# OMC_Unit_200316.net
KiCad netlist of a schematic drawn in Altium Designer
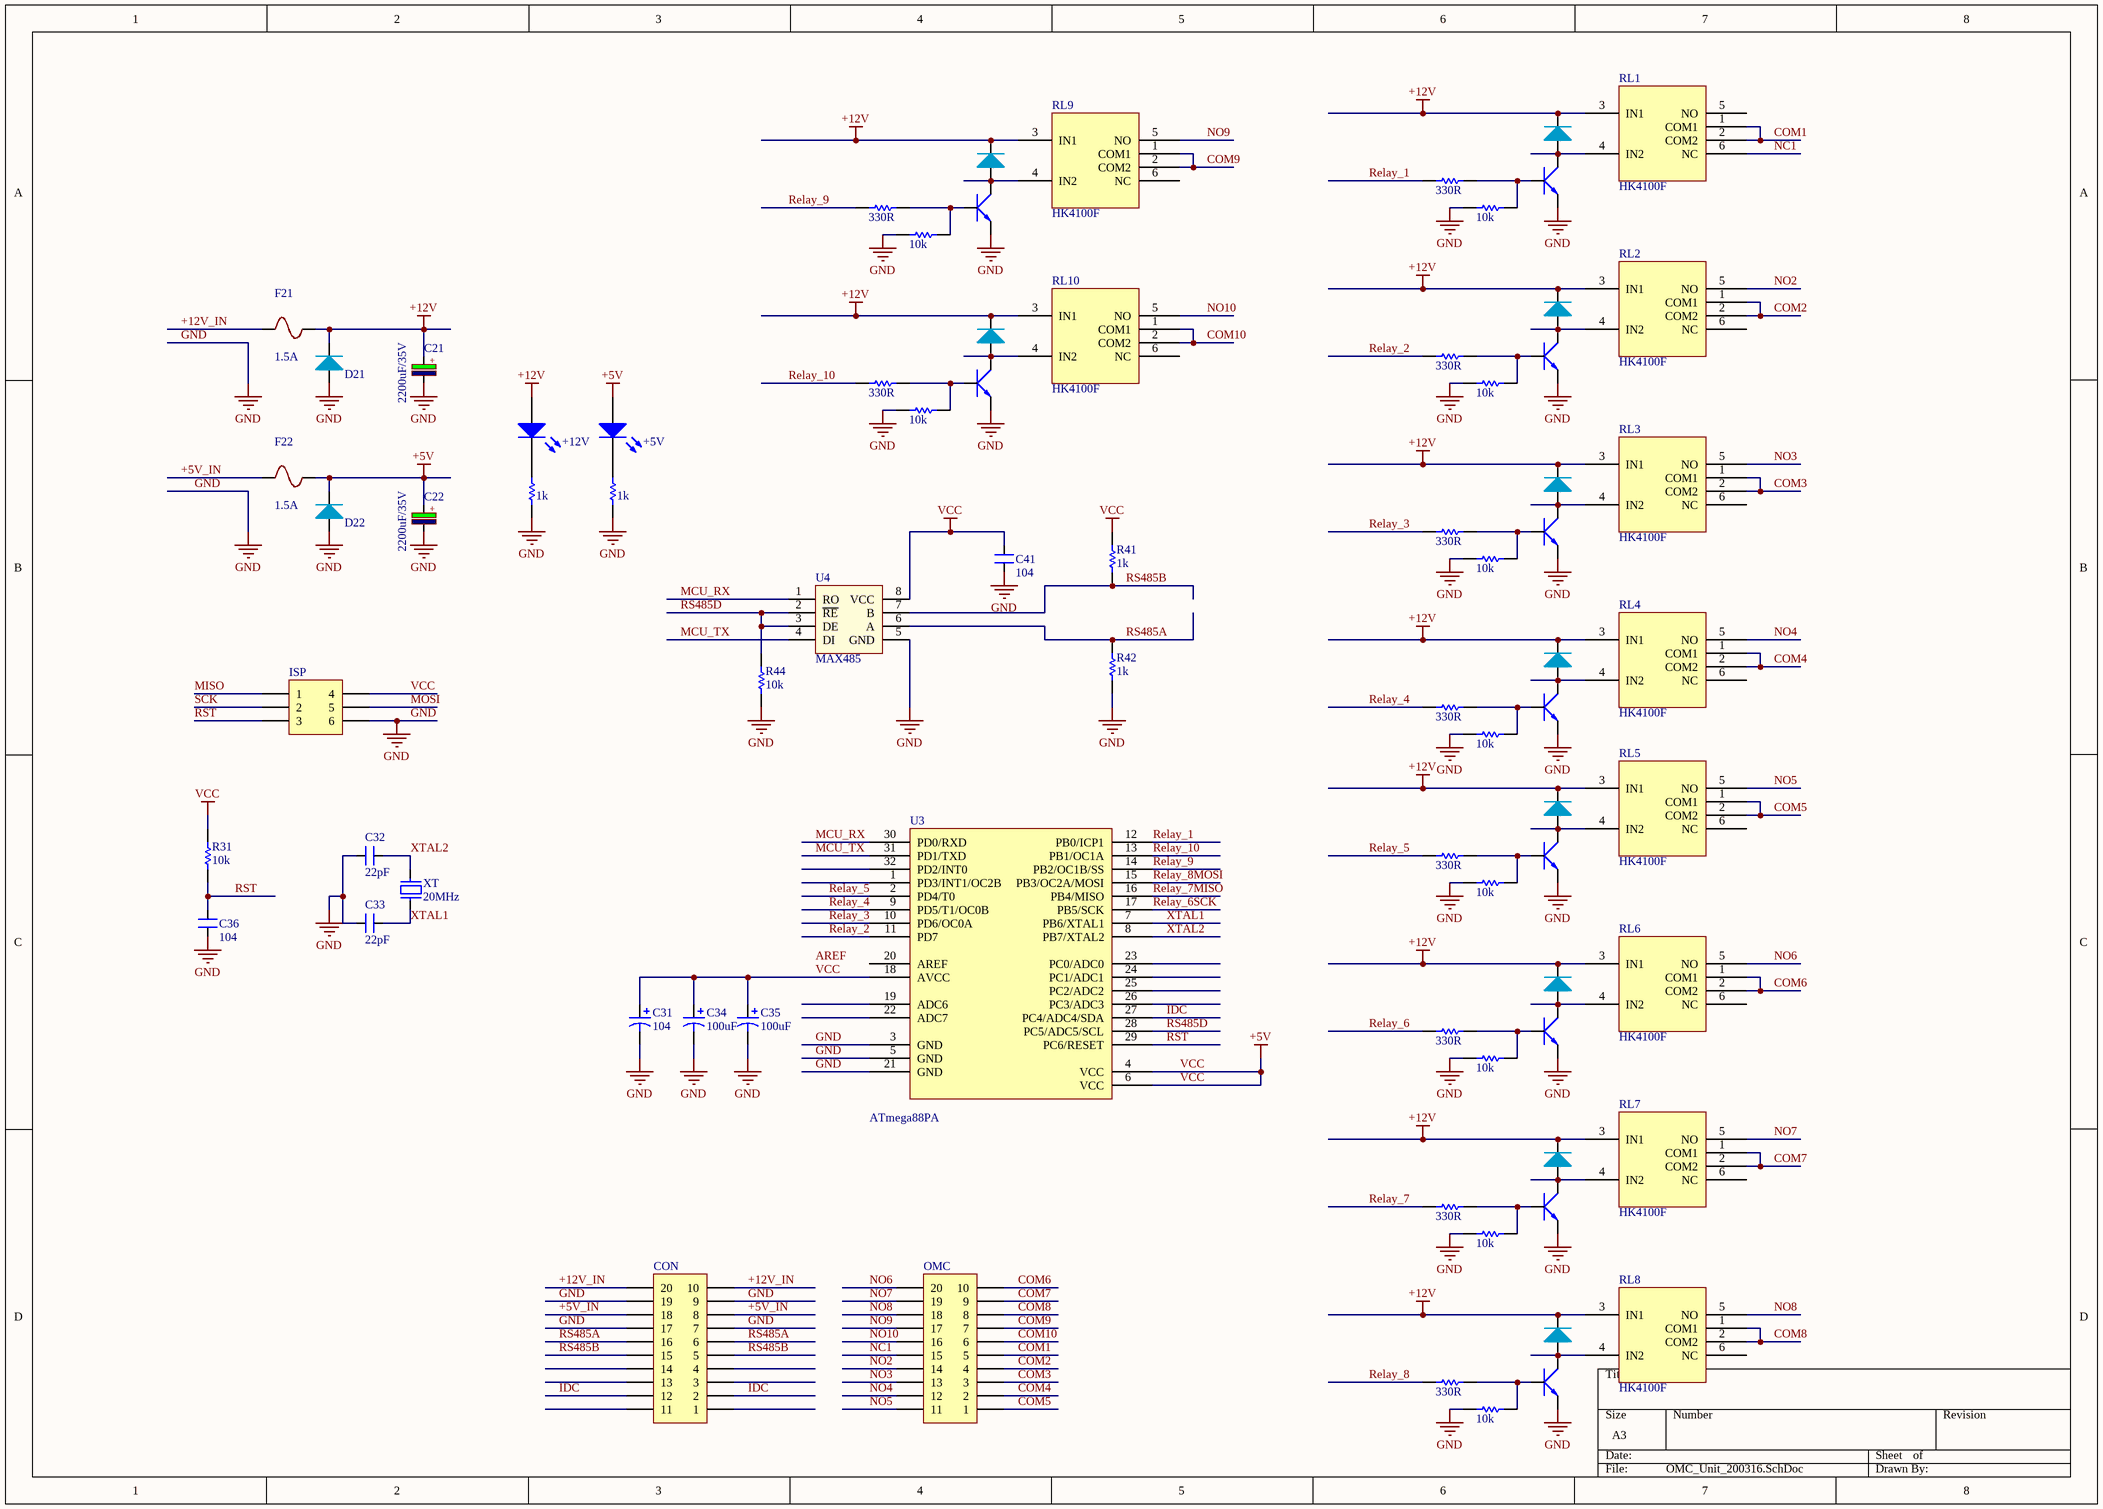
[diagram p0: OMC_Unit_200316.SchDoc]

(export (version "E")
  (design (tool "Eeschema 10.0.6"))
  (components
    (comp (ref "+5V") (value "Led") (footprint "LED 5mm RED") (libsource (lib "Tuan") (part "Led")))
    (comp (ref "+12V") (value "Led") (footprint "LED 5mm RED") (libsource (lib "Tuan") (part "Led")))
    (comp (ref "C21")
      (value "2200uF/35V")
      (footprint "PBL - SMD Packages:CAP_ELEC_SIZE_G")
      (description "Cap 1000uF/16V - 220uF/50V")
      (libsource (lib "heromap") (part "CP4"))
    )
    (comp (ref "C22")
      (value "2200uF/35V")
      (footprint "PBL - SMD Packages:CAP_ELEC_SIZE_G")
      (description "Cap 1000uF/16V - 220uF/50V")
      (libsource (lib "heromap") (part "CP4"))
    )
    (comp (ref "C31")
      (value "104")
      (footprint "CAPC2012N_F")
      (fields (field (name "Comment") "Cap"))
      (libsource (lib "Tuan") (part "Cap"))
    )
    (comp (ref "C32")
      (value "22pF")
      (footprint "CAPC1608N")
      (fields (field (name "Comment") "CAP NP"))
      (libsource (lib "Tuan") (part "CAP NP"))
    )
    (comp (ref "C33")
      (value "22pF")
      (footprint "CAPC1608N")
      (fields (field (name "Comment") "CAP NP"))
      (libsource (lib "Tuan") (part "CAP NP"))
    )
    (comp (ref "C34")
      (value "100uF")
      (footprint "CAPC2012N_F")
      (fields (field (name "Comment") "Cap"))
      (libsource (lib "Tuan") (part "Cap"))
    )
    (comp (ref "C35")
      (value "100uF")
      (footprint "CAPC2012N_F")
      (fields (field (name "Comment") "Cap"))
      (libsource (lib "Tuan") (part "Cap"))
    )
    (comp (ref "C36")
      (value "104")
      (footprint "CAPC1608N")
      (fields (field (name "Comment") "CAP NP"))
      (libsource (lib "Tuan") (part "CAP NP"))
    )
    (comp (ref "C41")
      (value "104")
      (footprint "CAPC2012N_F")
      (fields (field (name "Comment") "100nF/104"))
      (libsource (lib "Tuan") (part "CAP NP"))
    )
    (comp (ref "CON")
      (value "Header 10X2A")
      (footprint "OMC10")
      (description "Header, 10-Pin, Dual row")
      (fields (field (name "PUBLISHER") "Altium Limited"))
      (libsource (lib "Miscellaneous Connectors") (part "Header 10X2A"))
    )
    (comp (ref "D21") (value "Diode") (footprint "DO-214AC") (libsource (lib "Tuan") (part "Diode")))
    (comp (ref "D22") (value "Diode") (footprint "DO-214AC") (libsource (lib "Tuan") (part "Diode")))
    (comp (ref "Do1") (value "M7") (footprint "DO-214AC") (libsource (lib "Tuan") (part "Diode")))
    (comp (ref "Do2") (value "M7") (footprint "DO-214AC") (libsource (lib "Tuan") (part "Diode")))
    (comp (ref "Do3") (value "M7") (footprint "DO-214AC") (libsource (lib "Tuan") (part "Diode")))
    (comp (ref "Do4") (value "M7") (footprint "DO-214AC") (libsource (lib "Tuan") (part "Diode")))
    (comp (ref "Do5") (value "M7") (footprint "DO-214AC") (libsource (lib "Tuan") (part "Diode")))
    (comp (ref "Do6") (value "M7") (footprint "DO-214AC") (libsource (lib "Tuan") (part "Diode")))
    (comp (ref "Do7") (value "M7") (footprint "DO-214AC") (libsource (lib "Tuan") (part "Diode")))
    (comp (ref "Do8") (value "M7") (footprint "DO-214AC") (libsource (lib "Tuan") (part "Diode")))
    (comp (ref "Do9") (value "M7") (footprint "DO-214AC") (libsource (lib "Tuan") (part "Diode")))
    (comp (ref "Do10") (value "M7") (footprint "DO-214AC") (libsource (lib "Tuan") (part "Diode")))
    (comp (ref "F21") (value "1.5A") (footprint "FUSE_SR-5-BK") (libsource (lib "Tuan") (part "Fuse")))
    (comp (ref "F22") (value "1.5A") (footprint "FUSE_SR-5-BK") (libsource (lib "Tuan") (part "Fuse")))
    (comp (ref "ISP")
      (value "Header 3X2A")
      (footprint "HDR2X3_CEN")
      (description "Header, 3-Pin, Dual row")
      (fields (field (name "PUBLISHER") "Altium Limited"))
      (libsource (lib "Miscellaneous Connectors") (part "Header 3X2A"))
    )
    (comp (ref "OMC")
      (value "Header 10X2A")
      (footprint "OMC10")
      (description "Header, 10-Pin, Dual row")
      (fields (field (name "PUBLISHER") "Altium Limited"))
      (libsource (lib "Miscellaneous Connectors") (part "Header 10X2A"))
    )
    (comp (ref "Qo1")
      (value "C828")
      (footprint "SOT23 TOP")
      (description "Transistor C828 C1815....")
      (libsource (lib "Tuan") (part "NPN"))
    )
    (comp (ref "Qo2")
      (value "C828")
      (footprint "SOT23 TOP")
      (description "Transistor C828 C1815....")
      (libsource (lib "Tuan") (part "NPN"))
    )
    (comp (ref "Qo3")
      (value "C828")
      (footprint "SOT23 TOP")
      (description "Transistor C828 C1815....")
      (libsource (lib "Tuan") (part "NPN"))
    )
    (comp (ref "Qo4")
      (value "C828")
      (footprint "SOT23 TOP")
      (description "Transistor C828 C1815....")
      (libsource (lib "Tuan") (part "NPN"))
    )
    (comp (ref "Qo5")
      (value "C828")
      (footprint "SOT23 TOP")
      (description "Transistor C828 C1815....")
      (libsource (lib "Tuan") (part "NPN"))
    )
    (comp (ref "Qo6")
      (value "C828")
      (footprint "SOT23 TOP")
      (description "Transistor C828 C1815....")
      (libsource (lib "Tuan") (part "NPN"))
    )
    (comp (ref "Qo7")
      (value "C828")
      (footprint "SOT23 TOP")
      (description "Transistor C828 C1815....")
      (libsource (lib "Tuan") (part "NPN"))
    )
    (comp (ref "Qo8")
      (value "C828")
      (footprint "SOT23 TOP")
      (description "Transistor C828 C1815....")
      (libsource (lib "Tuan") (part "NPN"))
    )
    (comp (ref "Qo9")
      (value "C828")
      (footprint "SOT23 TOP")
      (description "Transistor C828 C1815....")
      (libsource (lib "Tuan") (part "NPN"))
    )
    (comp (ref "Qo10")
      (value "C828")
      (footprint "SOT23 TOP")
      (description "Transistor C828 C1815....")
      (libsource (lib "Tuan") (part "NPN"))
    )
    (comp (ref "R21")
      (value "1k")
      (footprint "RESC2012N_F")
      (fields (field (name "Comment") "Res_0805_1k"))
      (libsource (lib "Tuan") (part "Res"))
    )
    (comp (ref "R22")
      (value "1k")
      (footprint "RESC2012N_F")
      (fields (field (name "Comment") "Res_0805_1k"))
      (libsource (lib "Tuan") (part "Res"))
    )
    (comp (ref "R31")
      (value "10k")
      (footprint "RESC1608N_ZERO")
      (fields (field (name "Comment") "Res"))
      (libsource (lib "Tuan") (part "Res"))
    )
    (comp (ref "R41")
      (value "1k")
      (footprint "RESC1608N_ZERO")
      (description "Tro dan")
      (libsource (lib "GPS_Clock_v12") (part "Res"))
    )
    (comp (ref "R42")
      (value "1k")
      (footprint "RESC1608N_ZERO")
      (description "Tro dan")
      (libsource (lib "GPS_Clock_v12") (part "Res"))
    )
    (comp (ref "R44")
      (value "10k")
      (footprint "RESC1608N_ZERO")
      (description "Tro dan")
      (fields (field (name "Comment") "330R"))
      (libsource (lib "GPS_Clock_v12") (part "Res"))
    )
    (comp (ref "RL1") (value "HK4100F") (footprint "HK4100F") (libsource (lib "Tuan") (part "HK4100F")))
    (comp (ref "RL2") (value "HK4100F") (footprint "HK4100F") (libsource (lib "Tuan") (part "HK4100F")))
    (comp (ref "RL3") (value "HK4100F") (footprint "HK4100F") (libsource (lib "Tuan") (part "HK4100F")))
    (comp (ref "RL4") (value "HK4100F") (footprint "HK4100F") (libsource (lib "Tuan") (part "HK4100F")))
    (comp (ref "RL5") (value "HK4100F") (footprint "HK4100F") (libsource (lib "Tuan") (part "HK4100F")))
    (comp (ref "RL6") (value "HK4100F") (footprint "HK4100F") (libsource (lib "Tuan") (part "HK4100F")))
    (comp (ref "RL7") (value "HK4100F") (footprint "HK4100F") (libsource (lib "Tuan") (part "HK4100F")))
    (comp (ref "RL8") (value "HK4100F") (footprint "HK4100F") (libsource (lib "Tuan") (part "HK4100F")))
    (comp (ref "RL9") (value "HK4100F") (footprint "HK4100F") (libsource (lib "Tuan") (part "HK4100F")))
    (comp (ref "RL10") (value "HK4100F") (footprint "HK4100F") (libsource (lib "Tuan") (part "HK4100F")))
    (comp (ref "Rp1")
      (value "10k")
      (footprint "RESC1608N_ZERO")
      (fields (field (name "Comment") "Res"))
      (libsource (lib "Tuan") (part "Res"))
    )
    (comp (ref "Rp2")
      (value "10k")
      (footprint "RESC1608N_ZERO")
      (fields (field (name "Comment") "Res"))
      (libsource (lib "Tuan") (part "Res"))
    )
    (comp (ref "Rp3")
      (value "10k")
      (footprint "RESC1608N_ZERO")
      (fields (field (name "Comment") "Res"))
      (libsource (lib "Tuan") (part "Res"))
    )
    (comp (ref "Rp4")
      (value "10k")
      (footprint "RESC1608N_ZERO")
      (fields (field (name "Comment") "Res"))
      (libsource (lib "Tuan") (part "Res"))
    )
    (comp (ref "Rp5")
      (value "10k")
      (footprint "RESC1608N_ZERO")
      (fields (field (name "Comment") "Res"))
      (libsource (lib "Tuan") (part "Res"))
    )
    (comp (ref "Rp6")
      (value "10k")
      (footprint "RESC1608N_ZERO")
      (fields (field (name "Comment") "Res"))
      (libsource (lib "Tuan") (part "Res"))
    )
    (comp (ref "Rp7")
      (value "10k")
      (footprint "RESC1608N_ZERO")
      (fields (field (name "Comment") "Res"))
      (libsource (lib "Tuan") (part "Res"))
    )
    (comp (ref "Rp8")
      (value "10k")
      (footprint "RESC1608N_ZERO")
      (fields (field (name "Comment") "Res"))
      (libsource (lib "Tuan") (part "Res"))
    )
    (comp (ref "Rp9")
      (value "10k")
      (footprint "RESC1608N_ZERO")
      (fields (field (name "Comment") "Res"))
      (libsource (lib "Tuan") (part "Res"))
    )
    (comp (ref "Rp10")
      (value "10k")
      (footprint "RESC1608N_ZERO")
      (fields (field (name "Comment") "Res"))
      (libsource (lib "Tuan") (part "Res"))
    )
    (comp (ref "Rr1")
      (value "330R")
      (footprint "RESC1608N_ZERO")
      (fields (field (name "Comment") "Res"))
      (libsource (lib "Tuan") (part "Res"))
    )
    (comp (ref "Rr2")
      (value "330R")
      (footprint "RESC1608N_ZERO")
      (fields (field (name "Comment") "Res"))
      (libsource (lib "Tuan") (part "Res"))
    )
    (comp (ref "Rr3")
      (value "330R")
      (footprint "RESC1608N_ZERO")
      (fields (field (name "Comment") "Res"))
      (libsource (lib "Tuan") (part "Res"))
    )
    (comp (ref "Rr4")
      (value "330R")
      (footprint "RESC1608N_ZERO")
      (fields (field (name "Comment") "Res"))
      (libsource (lib "Tuan") (part "Res"))
    )
    (comp (ref "Rr5")
      (value "330R")
      (footprint "RESC1608N_ZERO")
      (fields (field (name "Comment") "Res"))
      (libsource (lib "Tuan") (part "Res"))
    )
    (comp (ref "Rr6")
      (value "330R")
      (footprint "RESC1608N_ZERO")
      (fields (field (name "Comment") "Res"))
      (libsource (lib "Tuan") (part "Res"))
    )
    (comp (ref "Rr7")
      (value "330R")
      (footprint "RESC1608N_ZERO")
      (fields (field (name "Comment") "Res"))
      (libsource (lib "Tuan") (part "Res"))
    )
    (comp (ref "Rr8")
      (value "330R")
      (footprint "RESC1608N_ZERO")
      (fields (field (name "Comment") "Res"))
      (libsource (lib "Tuan") (part "Res"))
    )
    (comp (ref "Rr9")
      (value "330R")
      (footprint "RESC1608N_ZERO")
      (fields (field (name "Comment") "Res"))
      (libsource (lib "Tuan") (part "Res"))
    )
    (comp (ref "Rr10")
      (value "330R")
      (footprint "RESC1608N_ZERO")
      (fields (field (name "Comment") "Res"))
      (libsource (lib "Tuan") (part "Res"))
    )
    (comp (ref "U3")
      (value "ATmega88PA")
      (footprint "32PIN")
      (description "ATmega48/168/328")
      (libsource (lib "Tuan") (part "ATmega48/168/328"))
    )
    (comp (ref "U4")
      (value "MAX485")
      (footprint "SO-8")
      (description "RS232 - RS485 (Same sn75176)")
      (libsource (lib "heromap") (part "MAX485"))
    )
    (comp (ref "XT") (value "20MHz") (footprint "XT2") (libsource (lib "Tuan") (part "Crystal")))
  )
  (nets
    (net (code "1") (name "+5V") (class "Default")
      (node (ref "+5V") (pin "1") (pinfunction "A_1") (pintype "passive"))
      (node (ref "C22") (pin "1") (pinfunction "1_1") (pintype "passive"))
      (node (ref "C31") (pin "1") (pinfunction "1_1") (pintype "passive"))
      (node (ref "C34") (pin "1") (pinfunction "1_1") (pintype "passive"))
      (node (ref "C35") (pin "1") (pinfunction "1_1") (pintype "passive"))
      (node (ref "C41") (pin "2") (pinfunction "2_2") (pintype "passive"))
      (node (ref "D22") (pin "2") (pinfunction "K_2") (pintype "passive"))
      (node (ref "F22") (pin "2") (pinfunction "2_2") (pintype "passive"))
      (node (ref "ISP") (pin "4") (pinfunction "4_4") (pintype "passive"))
      (node (ref "R31") (pin "2") (pinfunction "2_2") (pintype "passive"))
      (node (ref "R41") (pin "2") (pinfunction "2_2") (pintype "passive"))
      (node (ref "U3") (pin "18") (pinfunction "AVCC_18") (pintype "passive"))
      (node (ref "U3") (pin "4") (pinfunction "VCC_4") (pintype "passive"))
      (node (ref "U3") (pin "6") (pinfunction "VCC_6") (pintype "passive"))
      (node (ref "U4") (pin "8") (pinfunction "VCC_8") (pintype "passive"))
    )
    (net (code "2") (name "+12V") (class "Default")
      (node (ref "+12V") (pin "1") (pinfunction "A_1") (pintype "passive"))
      (node (ref "C21") (pin "1") (pinfunction "1_1") (pintype "passive"))
      (node (ref "D21") (pin "2") (pinfunction "K_2") (pintype "passive"))
      (node (ref "Do1") (pin "2") (pinfunction "K_2") (pintype "passive"))
      (node (ref "Do10") (pin "2") (pinfunction "K_2") (pintype "passive"))
      (node (ref "Do2") (pin "2") (pinfunction "K_2") (pintype "passive"))
      (node (ref "Do3") (pin "2") (pinfunction "K_2") (pintype "passive"))
      (node (ref "Do4") (pin "2") (pinfunction "K_2") (pintype "passive"))
      (node (ref "Do5") (pin "2") (pinfunction "K_2") (pintype "passive"))
      (node (ref "Do6") (pin "2") (pinfunction "K_2") (pintype "passive"))
      (node (ref "Do7") (pin "2") (pinfunction "K_2") (pintype "passive"))
      (node (ref "Do8") (pin "2") (pinfunction "K_2") (pintype "passive"))
      (node (ref "Do9") (pin "2") (pinfunction "K_2") (pintype "passive"))
      (node (ref "F21") (pin "2") (pinfunction "2_2") (pintype "passive"))
      (node (ref "RL1") (pin "3") (pinfunction "IN1_3") (pintype "passive"))
      (node (ref "RL10") (pin "3") (pinfunction "IN1_3") (pintype "passive"))
      (node (ref "RL2") (pin "3") (pinfunction "IN1_3") (pintype "passive"))
      (node (ref "RL3") (pin "3") (pinfunction "IN1_3") (pintype "passive"))
      (node (ref "RL4") (pin "3") (pinfunction "IN1_3") (pintype "passive"))
      (node (ref "RL5") (pin "3") (pinfunction "IN1_3") (pintype "passive"))
      (node (ref "RL6") (pin "3") (pinfunction "IN1_3") (pintype "passive"))
      (node (ref "RL7") (pin "3") (pinfunction "IN1_3") (pintype "passive"))
      (node (ref "RL8") (pin "3") (pinfunction "IN1_3") (pintype "passive"))
      (node (ref "RL9") (pin "3") (pinfunction "IN1_3") (pintype "passive"))
    )
    (net (code "3") (name "/+5V_IN") (class "Default")
      (node (ref "CON") (pin "18") (pinfunction "18_18") (pintype "passive"))
      (node (ref "CON") (pin "8") (pinfunction "8_8") (pintype "passive"))
      (node (ref "F22") (pin "1") (pinfunction "1_1") (pintype "passive"))
    )
    (net (code "4") (name "/+12V_IN") (class "Default")
      (node (ref "CON") (pin "10") (pinfunction "10_10") (pintype "passive"))
      (node (ref "CON") (pin "20") (pinfunction "20_20") (pintype "passive"))
      (node (ref "F21") (pin "1") (pinfunction "1_1") (pintype "passive"))
    )
    (net (code "6") (name "/COM1") (class "Default")
      (node (ref "OMC") (pin "5") (pinfunction "5_5") (pintype "passive"))
      (node (ref "RL1") (pin "1") (pinfunction "COM1_1") (pintype "passive"))
      (node (ref "RL1") (pin "2") (pinfunction "COM2_2") (pintype "passive"))
    )
    (net (code "7") (name "/COM2") (class "Default")
      (node (ref "OMC") (pin "4") (pinfunction "4_4") (pintype "passive"))
      (node (ref "RL2") (pin "1") (pinfunction "COM1_1") (pintype "passive"))
      (node (ref "RL2") (pin "2") (pinfunction "COM2_2") (pintype "passive"))
    )
    (net (code "8") (name "/COM3") (class "Default")
      (node (ref "OMC") (pin "3") (pinfunction "3_3") (pintype "passive"))
      (node (ref "RL3") (pin "1") (pinfunction "COM1_1") (pintype "passive"))
      (node (ref "RL3") (pin "2") (pinfunction "COM2_2") (pintype "passive"))
    )
    (net (code "9") (name "/COM4") (class "Default")
      (node (ref "OMC") (pin "2") (pinfunction "2_2") (pintype "passive"))
      (node (ref "RL4") (pin "1") (pinfunction "COM1_1") (pintype "passive"))
      (node (ref "RL4") (pin "2") (pinfunction "COM2_2") (pintype "passive"))
    )
    (net (code "10") (name "/COM5") (class "Default")
      (node (ref "OMC") (pin "1") (pinfunction "1_1") (pintype "passive"))
      (node (ref "RL5") (pin "1") (pinfunction "COM1_1") (pintype "passive"))
      (node (ref "RL5") (pin "2") (pinfunction "COM2_2") (pintype "passive"))
    )
    (net (code "11") (name "/COM6") (class "Default")
      (node (ref "OMC") (pin "10") (pinfunction "10_10") (pintype "passive"))
      (node (ref "RL6") (pin "1") (pinfunction "COM1_1") (pintype "passive"))
      (node (ref "RL6") (pin "2") (pinfunction "COM2_2") (pintype "passive"))
    )
    (net (code "12") (name "/COM7") (class "Default")
      (node (ref "OMC") (pin "9") (pinfunction "9_9") (pintype "passive"))
      (node (ref "RL7") (pin "1") (pinfunction "COM1_1") (pintype "passive"))
      (node (ref "RL7") (pin "2") (pinfunction "COM2_2") (pintype "passive"))
    )
    (net (code "13") (name "/COM8") (class "Default")
      (node (ref "OMC") (pin "8") (pinfunction "8_8") (pintype "passive"))
      (node (ref "RL8") (pin "1") (pinfunction "COM1_1") (pintype "passive"))
      (node (ref "RL8") (pin "2") (pinfunction "COM2_2") (pintype "passive"))
    )
    (net (code "14") (name "/COM9") (class "Default")
      (node (ref "OMC") (pin "7") (pinfunction "7_7") (pintype "passive"))
      (node (ref "RL9") (pin "1") (pinfunction "COM1_1") (pintype "passive"))
      (node (ref "RL9") (pin "2") (pinfunction "COM2_2") (pintype "passive"))
    )
    (net (code "15") (name "/COM10") (class "Default")
      (node (ref "OMC") (pin "6") (pinfunction "6_6") (pintype "passive"))
      (node (ref "RL10") (pin "1") (pinfunction "COM1_1") (pintype "passive"))
      (node (ref "RL10") (pin "2") (pinfunction "COM2_2") (pintype "passive"))
    )
    (net (code "16") (name "/IDC") (class "Default")
      (node (ref "CON") (pin "12") (pinfunction "12_12") (pintype "passive"))
      (node (ref "CON") (pin "2") (pinfunction "2_2") (pintype "passive"))
      (node (ref "U3") (pin "27") (pinfunction "PC4/ADC4/SDA_27") (pintype "passive"))
    )
    (net (code "17") (name "/MCU_RX") (class "Default")
      (node (ref "U3") (pin "30") (pinfunction "PD0/RXD_30") (pintype "passive"))
      (node (ref "U4") (pin "1") (pinfunction "RO_1") (pintype "passive"))
    )
    (net (code "18") (name "/MCU_TX") (class "Default")
      (node (ref "U3") (pin "31") (pinfunction "PD1/TXD_31") (pintype "passive"))
      (node (ref "U4") (pin "4") (pinfunction "DI_4") (pintype "passive"))
    )
    (net (code "19") (name "/MISO") (class "Default")
      (node (ref "ISP") (pin "1") (pinfunction "1_1") (pintype "passive"))
      (node (ref "Rr7") (pin "1") (pinfunction "1_1") (pintype "passive"))
      (node (ref "U3") (pin "16") (pinfunction "PB4/MISO_16") (pintype "passive"))
    )
    (net (code "20") (name "/MOSI") (class "Default")
      (node (ref "ISP") (pin "5") (pinfunction "5_5") (pintype "passive"))
      (node (ref "Rr8") (pin "1") (pinfunction "1_1") (pintype "passive"))
      (node (ref "U3") (pin "15") (pinfunction "PB3/OC2A/MOSI_15") (pintype "passive"))
    )
    (net (code "21") (name "/NC1") (class "Default")
      (node (ref "OMC") (pin "15") (pinfunction "15_15") (pintype "passive"))
      (node (ref "RL1") (pin "6") (pinfunction "NC_6") (pintype "passive"))
    )
    (net (code "22") (name "/NO2") (class "Default")
      (node (ref "OMC") (pin "14") (pinfunction "14_14") (pintype "passive"))
      (node (ref "RL2") (pin "5") (pinfunction "NO_5") (pintype "passive"))
    )
    (net (code "23") (name "/NO3") (class "Default")
      (node (ref "OMC") (pin "13") (pinfunction "13_13") (pintype "passive"))
      (node (ref "RL3") (pin "5") (pinfunction "NO_5") (pintype "passive"))
    )
    (net (code "24") (name "/NO4") (class "Default")
      (node (ref "OMC") (pin "12") (pinfunction "12_12") (pintype "passive"))
      (node (ref "RL4") (pin "5") (pinfunction "NO_5") (pintype "passive"))
    )
    (net (code "25") (name "/NO5") (class "Default")
      (node (ref "OMC") (pin "11") (pinfunction "11_11") (pintype "passive"))
      (node (ref "RL5") (pin "5") (pinfunction "NO_5") (pintype "passive"))
    )
    (net (code "26") (name "/NO6") (class "Default")
      (node (ref "OMC") (pin "20") (pinfunction "20_20") (pintype "passive"))
      (node (ref "RL6") (pin "5") (pinfunction "NO_5") (pintype "passive"))
    )
    (net (code "27") (name "/NO7") (class "Default")
      (node (ref "OMC") (pin "19") (pinfunction "19_19") (pintype "passive"))
      (node (ref "RL7") (pin "5") (pinfunction "NO_5") (pintype "passive"))
    )
    (net (code "28") (name "/NO8") (class "Default")
      (node (ref "OMC") (pin "18") (pinfunction "18_18") (pintype "passive"))
      (node (ref "RL8") (pin "5") (pinfunction "NO_5") (pintype "passive"))
    )
    (net (code "29") (name "/NO9") (class "Default")
      (node (ref "OMC") (pin "17") (pinfunction "17_17") (pintype "passive"))
      (node (ref "RL9") (pin "5") (pinfunction "NO_5") (pintype "passive"))
    )
    (net (code "30") (name "/NO10") (class "Default")
      (node (ref "OMC") (pin "16") (pinfunction "16_16") (pintype "passive"))
      (node (ref "RL10") (pin "5") (pinfunction "NO_5") (pintype "passive"))
    )
    (net (code "31") (name "/RS485A") (class "Default")
      (node (ref "CON") (pin "16") (pinfunction "16_16") (pintype "passive"))
      (node (ref "CON") (pin "6") (pinfunction "6_6") (pintype "passive"))
      (node (ref "R42") (pin "2") (pinfunction "2_2") (pintype "passive"))
      (node (ref "U4") (pin "6") (pinfunction "A_6") (pintype "passive"))
    )
    (net (code "32") (name "/RS485B") (class "Default")
      (node (ref "CON") (pin "15") (pinfunction "15_15") (pintype "passive"))
      (node (ref "CON") (pin "5") (pinfunction "5_5") (pintype "passive"))
      (node (ref "R41") (pin "1") (pinfunction "1_1") (pintype "passive"))
      (node (ref "U4") (pin "7") (pinfunction "B_7") (pintype "passive"))
    )
    (net (code "33") (name "/RS485D") (class "Default")
      (node (ref "R44") (pin "2") (pinfunction "2_2") (pintype "passive"))
      (node (ref "U3") (pin "28") (pinfunction "PC5/ADC5/SCL_28") (pintype "passive"))
      (node (ref "U4") (pin "2") (pinfunction "~{RE}_2") (pintype "passive"))
      (node (ref "U4") (pin "3") (pinfunction "DE_3") (pintype "passive"))
    )
    (net (code "34") (name "/RST") (class "Default")
      (node (ref "C36") (pin "2") (pinfunction "2_2") (pintype "passive"))
      (node (ref "ISP") (pin "3") (pinfunction "3_3") (pintype "passive"))
      (node (ref "R31") (pin "1") (pinfunction "1_1") (pintype "passive"))
      (node (ref "U3") (pin "29") (pinfunction "PC6/RESET_29") (pintype "passive"))
    )
    (net (code "35") (name "/Relay_1") (class "Default")
      (node (ref "Rr1") (pin "1") (pinfunction "1_1") (pintype "passive"))
      (node (ref "U3") (pin "12") (pinfunction "PB0/ICP1_12") (pintype "passive"))
    )
    (net (code "36") (name "/Relay_2") (class "Default")
      (node (ref "Rr2") (pin "1") (pinfunction "1_1") (pintype "passive"))
      (node (ref "U3") (pin "11") (pinfunction "PD7_11") (pintype "passive"))
    )
    (net (code "37") (name "/Relay_3") (class "Default")
      (node (ref "Rr3") (pin "1") (pinfunction "1_1") (pintype "passive"))
      (node (ref "U3") (pin "10") (pinfunction "PD6/OC0A_10") (pintype "passive"))
    )
    (net (code "38") (name "/Relay_4") (class "Default")
      (node (ref "Rr4") (pin "1") (pinfunction "1_1") (pintype "passive"))
      (node (ref "U3") (pin "9") (pinfunction "PD5/T1/OC0B_9") (pintype "passive"))
    )
    (net (code "39") (name "/Relay_5") (class "Default")
      (node (ref "Rr5") (pin "1") (pinfunction "1_1") (pintype "passive"))
      (node (ref "U3") (pin "2") (pinfunction "PD4/T0_2") (pintype "passive"))
    )
    (net (code "40") (name "/Relay_6") (class "Default")
      (node (ref "ISP") (pin "2") (pinfunction "2_2") (pintype "passive"))
      (node (ref "Rr6") (pin "1") (pinfunction "1_1") (pintype "passive"))
      (node (ref "U3") (pin "17") (pinfunction "PB5/SCK_17") (pintype "passive"))
    )
    (net (code "41") (name "/Relay_9") (class "Default")
      (node (ref "Rr9") (pin "1") (pinfunction "1_1") (pintype "passive"))
      (node (ref "U3") (pin "14") (pinfunction "PB2/OC1B/SS_14") (pintype "passive"))
    )
    (net (code "42") (name "/Relay_10") (class "Default")
      (node (ref "Rr10") (pin "1") (pinfunction "1_1") (pintype "passive"))
      (node (ref "U3") (pin "13") (pinfunction "PB1/OC1A_13") (pintype "passive"))
    )
    (net (code "43") (name "/XTAL1") (class "Default")
      (node (ref "C33") (pin "1") (pinfunction "1_1") (pintype "passive"))
      (node (ref "U3") (pin "7") (pinfunction "PB6/XTAL1_7") (pintype "passive"))
      (node (ref "XT") (pin "1") (pinfunction "1_1") (pintype "passive"))
    )
    (net (code "44") (name "/XTAL2") (class "Default")
      (node (ref "C32") (pin "1") (pinfunction "1_1") (pintype "passive"))
      (node (ref "U3") (pin "8") (pinfunction "PB7/XTAL2_8") (pintype "passive"))
      (node (ref "XT") (pin "2") (pinfunction "2_2") (pintype "passive"))
    )
    (net (code "45") (name "GND") (class "Default")
      (node (ref "C21") (pin "2") (pinfunction "2_2") (pintype "passive"))
      (node (ref "C22") (pin "2") (pinfunction "2_2") (pintype "passive"))
      (node (ref "C31") (pin "2") (pinfunction "2_2") (pintype "passive"))
      (node (ref "C32") (pin "2") (pinfunction "2_2") (pintype "passive"))
      (node (ref "C33") (pin "2") (pinfunction "2_2") (pintype "passive"))
      (node (ref "C34") (pin "2") (pinfunction "2_2") (pintype "passive"))
      (node (ref "C35") (pin "2") (pinfunction "2_2") (pintype "passive"))
      (node (ref "C36") (pin "1") (pinfunction "1_1") (pintype "passive"))
      (node (ref "C41") (pin "1") (pinfunction "1_1") (pintype "passive"))
      (node (ref "CON") (pin "17") (pinfunction "17_17") (pintype "passive"))
      (node (ref "CON") (pin "19") (pinfunction "19_19") (pintype "passive"))
      (node (ref "CON") (pin "7") (pinfunction "7_7") (pintype "passive"))
      (node (ref "CON") (pin "9") (pinfunction "9_9") (pintype "passive"))
      (node (ref "D21") (pin "1") (pinfunction "A_1") (pintype "passive"))
      (node (ref "D22") (pin "1") (pinfunction "A_1") (pintype "passive"))
      (node (ref "ISP") (pin "6") (pinfunction "6_6") (pintype "passive"))
      (node (ref "Qo1") (pin "3") (pinfunction "E_3") (pintype "passive"))
      (node (ref "Qo10") (pin "3") (pinfunction "E_3") (pintype "passive"))
      (node (ref "Qo2") (pin "3") (pinfunction "E_3") (pintype "passive"))
      (node (ref "Qo3") (pin "3") (pinfunction "E_3") (pintype "passive"))
      (node (ref "Qo4") (pin "3") (pinfunction "E_3") (pintype "passive"))
      (node (ref "Qo5") (pin "3") (pinfunction "E_3") (pintype "passive"))
      (node (ref "Qo6") (pin "3") (pinfunction "E_3") (pintype "passive"))
      (node (ref "Qo7") (pin "3") (pinfunction "E_3") (pintype "passive"))
      (node (ref "Qo8") (pin "3") (pinfunction "E_3") (pintype "passive"))
      (node (ref "Qo9") (pin "3") (pinfunction "E_3") (pintype "passive"))
      (node (ref "R21") (pin "2") (pinfunction "2_2") (pintype "passive"))
      (node (ref "R22") (pin "2") (pinfunction "2_2") (pintype "passive"))
      (node (ref "R42") (pin "1") (pinfunction "1_1") (pintype "passive"))
      (node (ref "R44") (pin "1") (pinfunction "1_1") (pintype "passive"))
      (node (ref "Rp1") (pin "1") (pinfunction "1_1") (pintype "passive"))
      (node (ref "Rp10") (pin "1") (pinfunction "1_1") (pintype "passive"))
      (node (ref "Rp2") (pin "1") (pinfunction "1_1") (pintype "passive"))
      (node (ref "Rp3") (pin "1") (pinfunction "1_1") (pintype "passive"))
      (node (ref "Rp4") (pin "1") (pinfunction "1_1") (pintype "passive"))
      (node (ref "Rp5") (pin "1") (pinfunction "1_1") (pintype "passive"))
      (node (ref "Rp6") (pin "1") (pinfunction "1_1") (pintype "passive"))
      (node (ref "Rp7") (pin "1") (pinfunction "1_1") (pintype "passive"))
      (node (ref "Rp8") (pin "1") (pinfunction "1_1") (pintype "passive"))
      (node (ref "Rp9") (pin "1") (pinfunction "1_1") (pintype "passive"))
      (node (ref "U3") (pin "21") (pinfunction "GND_21") (pintype "power_in"))
      (node (ref "U3") (pin "3") (pinfunction "GND_3") (pintype "power_in"))
      (node (ref "U3") (pin "5") (pinfunction "GND_5") (pintype "power_in"))
      (node (ref "U4") (pin "5") (pinfunction "GND_5") (pintype "passive"))
    )
    (net (code "46") (name "Net-(+5V-K)") (class "Default")
      (node (ref "+5V") (pin "2") (pinfunction "K_2") (pintype "passive"))
      (node (ref "R22") (pin "1") (pinfunction "1_1") (pintype "passive"))
    )
    (net (code "47") (name "Net-(+12V-K)") (class "Default")
      (node (ref "+12V") (pin "2") (pinfunction "K_2") (pintype "passive"))
      (node (ref "R21") (pin "1") (pinfunction "1_1") (pintype "passive"))
    )
    (net (code "48") (name "Net-(Do1-A)") (class "Default")
      (node (ref "Do1") (pin "1") (pinfunction "A_1") (pintype "passive"))
      (node (ref "Qo1") (pin "2") (pinfunction "C_2") (pintype "passive"))
      (node (ref "RL1") (pin "4") (pinfunction "IN2_4") (pintype "passive"))
    )
    (net (code "49") (name "Net-(Do2-A)") (class "Default")
      (node (ref "Do2") (pin "1") (pinfunction "A_1") (pintype "passive"))
      (node (ref "Qo2") (pin "2") (pinfunction "C_2") (pintype "passive"))
      (node (ref "RL2") (pin "4") (pinfunction "IN2_4") (pintype "passive"))
    )
    (net (code "50") (name "Net-(Do3-A)") (class "Default")
      (node (ref "Do3") (pin "1") (pinfunction "A_1") (pintype "passive"))
      (node (ref "Qo3") (pin "2") (pinfunction "C_2") (pintype "passive"))
      (node (ref "RL3") (pin "4") (pinfunction "IN2_4") (pintype "passive"))
    )
    (net (code "51") (name "Net-(Do4-A)") (class "Default")
      (node (ref "Do4") (pin "1") (pinfunction "A_1") (pintype "passive"))
      (node (ref "Qo4") (pin "2") (pinfunction "C_2") (pintype "passive"))
      (node (ref "RL4") (pin "4") (pinfunction "IN2_4") (pintype "passive"))
    )
    (net (code "52") (name "Net-(Do5-A)") (class "Default")
      (node (ref "Do5") (pin "1") (pinfunction "A_1") (pintype "passive"))
      (node (ref "Qo5") (pin "2") (pinfunction "C_2") (pintype "passive"))
      (node (ref "RL5") (pin "4") (pinfunction "IN2_4") (pintype "passive"))
    )
    (net (code "53") (name "Net-(Do6-A)") (class "Default")
      (node (ref "Do6") (pin "1") (pinfunction "A_1") (pintype "passive"))
      (node (ref "Qo6") (pin "2") (pinfunction "C_2") (pintype "passive"))
      (node (ref "RL6") (pin "4") (pinfunction "IN2_4") (pintype "passive"))
    )
    (net (code "54") (name "Net-(Do7-A)") (class "Default")
      (node (ref "Do7") (pin "1") (pinfunction "A_1") (pintype "passive"))
      (node (ref "Qo7") (pin "2") (pinfunction "C_2") (pintype "passive"))
      (node (ref "RL7") (pin "4") (pinfunction "IN2_4") (pintype "passive"))
    )
    (net (code "55") (name "Net-(Do8-A)") (class "Default")
      (node (ref "Do8") (pin "1") (pinfunction "A_1") (pintype "passive"))
      (node (ref "Qo8") (pin "2") (pinfunction "C_2") (pintype "passive"))
      (node (ref "RL8") (pin "4") (pinfunction "IN2_4") (pintype "passive"))
    )
    (net (code "56") (name "Net-(Do9-A)") (class "Default")
      (node (ref "Do9") (pin "1") (pinfunction "A_1") (pintype "passive"))
      (node (ref "Qo9") (pin "2") (pinfunction "C_2") (pintype "passive"))
      (node (ref "RL9") (pin "4") (pinfunction "IN2_4") (pintype "passive"))
    )
    (net (code "57") (name "Net-(Do10-A)") (class "Default")
      (node (ref "Do10") (pin "1") (pinfunction "A_1") (pintype "passive"))
      (node (ref "Qo10") (pin "2") (pinfunction "C_2") (pintype "passive"))
      (node (ref "RL10") (pin "4") (pinfunction "IN2_4") (pintype "passive"))
    )
    (net (code "58") (name "Net-(Qo1-B)") (class "Default")
      (node (ref "Qo1") (pin "1") (pinfunction "B_1") (pintype "passive"))
      (node (ref "Rp1") (pin "2") (pinfunction "2_2") (pintype "passive"))
      (node (ref "Rr1") (pin "2") (pinfunction "2_2") (pintype "passive"))
    )
    (net (code "59") (name "Net-(Qo2-B)") (class "Default")
      (node (ref "Qo2") (pin "1") (pinfunction "B_1") (pintype "passive"))
      (node (ref "Rp2") (pin "2") (pinfunction "2_2") (pintype "passive"))
      (node (ref "Rr2") (pin "2") (pinfunction "2_2") (pintype "passive"))
    )
    (net (code "60") (name "Net-(Qo3-B)") (class "Default")
      (node (ref "Qo3") (pin "1") (pinfunction "B_1") (pintype "passive"))
      (node (ref "Rp3") (pin "2") (pinfunction "2_2") (pintype "passive"))
      (node (ref "Rr3") (pin "2") (pinfunction "2_2") (pintype "passive"))
    )
    (net (code "61") (name "Net-(Qo4-B)") (class "Default")
      (node (ref "Qo4") (pin "1") (pinfunction "B_1") (pintype "passive"))
      (node (ref "Rp4") (pin "2") (pinfunction "2_2") (pintype "passive"))
      (node (ref "Rr4") (pin "2") (pinfunction "2_2") (pintype "passive"))
    )
    (net (code "62") (name "Net-(Qo5-B)") (class "Default")
      (node (ref "Qo5") (pin "1") (pinfunction "B_1") (pintype "passive"))
      (node (ref "Rp5") (pin "2") (pinfunction "2_2") (pintype "passive"))
      (node (ref "Rr5") (pin "2") (pinfunction "2_2") (pintype "passive"))
    )
    (net (code "63") (name "Net-(Qo6-B)") (class "Default")
      (node (ref "Qo6") (pin "1") (pinfunction "B_1") (pintype "passive"))
      (node (ref "Rp6") (pin "2") (pinfunction "2_2") (pintype "passive"))
      (node (ref "Rr6") (pin "2") (pinfunction "2_2") (pintype "passive"))
    )
    (net (code "64") (name "Net-(Qo7-B)") (class "Default")
      (node (ref "Qo7") (pin "1") (pinfunction "B_1") (pintype "passive"))
      (node (ref "Rp7") (pin "2") (pinfunction "2_2") (pintype "passive"))
      (node (ref "Rr7") (pin "2") (pinfunction "2_2") (pintype "passive"))
    )
    (net (code "65") (name "Net-(Qo8-B)") (class "Default")
      (node (ref "Qo8") (pin "1") (pinfunction "B_1") (pintype "passive"))
      (node (ref "Rp8") (pin "2") (pinfunction "2_2") (pintype "passive"))
      (node (ref "Rr8") (pin "2") (pinfunction "2_2") (pintype "passive"))
    )
    (net (code "66") (name "Net-(Qo9-B)") (class "Default")
      (node (ref "Qo9") (pin "1") (pinfunction "B_1") (pintype "passive"))
      (node (ref "Rp9") (pin "2") (pinfunction "2_2") (pintype "passive"))
      (node (ref "Rr9") (pin "2") (pinfunction "2_2") (pintype "passive"))
    )
    (net (code "67") (name "Net-(Qo10-B)") (class "Default")
      (node (ref "Qo10") (pin "1") (pinfunction "B_1") (pintype "passive"))
      (node (ref "Rp10") (pin "2") (pinfunction "2_2") (pintype "passive"))
      (node (ref "Rr10") (pin "2") (pinfunction "2_2") (pintype "passive"))
    )
    (net (code "68") (name "unconnected-(CON-Pad1)") (class "Default")
      (node (ref "CON") (pin "1") (pinfunction "1_1") (pintype "passive"))
    )
    (net (code "69") (name "unconnected-(CON-Pad3)") (class "Default")
      (node (ref "CON") (pin "3") (pinfunction "3_3") (pintype "passive"))
    )
    (net (code "70") (name "unconnected-(CON-Pad4)") (class "Default")
      (node (ref "CON") (pin "4") (pinfunction "4_4") (pintype "passive"))
    )
    (net (code "71") (name "unconnected-(CON-Pad11)") (class "Default")
      (node (ref "CON") (pin "11") (pinfunction "11_11") (pintype "passive"))
    )
    (net (code "72") (name "unconnected-(CON-Pad13)") (class "Default")
      (node (ref "CON") (pin "13") (pinfunction "13_13") (pintype "passive"))
    )
    (net (code "73") (name "unconnected-(CON-Pad14)") (class "Default")
      (node (ref "CON") (pin "14") (pinfunction "14_14") (pintype "passive"))
    )
    (net (code "74") (name "unconnected-(RL1-NO-Pad5)") (class "Default")
      (node (ref "RL1") (pin "5") (pinfunction "NO_5") (pintype "passive"))
    )
    (net (code "75") (name "unconnected-(RL2-NC-Pad6)") (class "Default")
      (node (ref "RL2") (pin "6") (pinfunction "NC_6") (pintype "passive"))
    )
    (net (code "76") (name "unconnected-(RL3-NC-Pad6)") (class "Default")
      (node (ref "RL3") (pin "6") (pinfunction "NC_6") (pintype "passive"))
    )
    (net (code "77") (name "unconnected-(RL4-NC-Pad6)") (class "Default")
      (node (ref "RL4") (pin "6") (pinfunction "NC_6") (pintype "passive"))
    )
    (net (code "78") (name "unconnected-(RL5-NC-Pad6)") (class "Default")
      (node (ref "RL5") (pin "6") (pinfunction "NC_6") (pintype "passive"))
    )
    (net (code "79") (name "unconnected-(RL6-NC-Pad6)") (class "Default")
      (node (ref "RL6") (pin "6") (pinfunction "NC_6") (pintype "passive"))
    )
    (net (code "80") (name "unconnected-(RL7-NC-Pad6)") (class "Default")
      (node (ref "RL7") (pin "6") (pinfunction "NC_6") (pintype "passive"))
    )
    (net (code "81") (name "unconnected-(RL8-NC-Pad6)") (class "Default")
      (node (ref "RL8") (pin "6") (pinfunction "NC_6") (pintype "passive"))
    )
    (net (code "82") (name "unconnected-(RL9-NC-Pad6)") (class "Default")
      (node (ref "RL9") (pin "6") (pinfunction "NC_6") (pintype "passive"))
    )
    (net (code "83") (name "unconnected-(RL10-NC-Pad6)") (class "Default")
      (node (ref "RL10") (pin "6") (pinfunction "NC_6") (pintype "passive"))
    )
    (net (code "84") (name "unconnected-(U3-ADC6-Pad19)") (class "Default")
      (node (ref "U3") (pin "19") (pinfunction "ADC6_19") (pintype "passive"))
    )
    (net (code "85") (name "unconnected-(U3-ADC7-Pad22)") (class "Default")
      (node (ref "U3") (pin "22") (pinfunction "ADC7_22") (pintype "passive"))
    )
    (net (code "86") (name "unconnected-(U3-AREF-Pad20)") (class "Default")
      (node (ref "U3") (pin "20") (pinfunction "AREF_20") (pintype "passive"))
    )
    (net (code "87") (name "unconnected-(U3-PC0{slash}ADC0-Pad23)") (class "Default")
      (node (ref "U3") (pin "23") (pinfunction "PC0/ADC0_23") (pintype "passive"))
    )
    (net (code "88") (name "unconnected-(U3-PC1{slash}ADC1-Pad24)") (class "Default")
      (node (ref "U3") (pin "24") (pinfunction "PC1/ADC1_24") (pintype "passive"))
    )
    (net (code "89") (name "unconnected-(U3-PC2{slash}ADC2-Pad25)") (class "Default")
      (node (ref "U3") (pin "25") (pinfunction "PC2/ADC2_25") (pintype "passive"))
    )
    (net (code "90") (name "unconnected-(U3-PC3{slash}ADC3-Pad26)") (class "Default")
      (node (ref "U3") (pin "26") (pinfunction "PC3/ADC3_26") (pintype "passive"))
    )
    (net (code "91") (name "unconnected-(U3-PD2{slash}INT0-Pad32)") (class "Default")
      (node (ref "U3") (pin "32") (pinfunction "PD2/INT0_32") (pintype "passive"))
    )
    (net (code "92") (name "unconnected-(U3-PD3{slash}INT1{slash}OC2B-Pad1)") (class "Default")
      (node (ref "U3") (pin "1") (pinfunction "PD3/INT1/OC2B_1") (pintype "passive"))
    )
  )
)
